# EasyRider.net
KiCad netlist of a schematic drawn in EAGLE
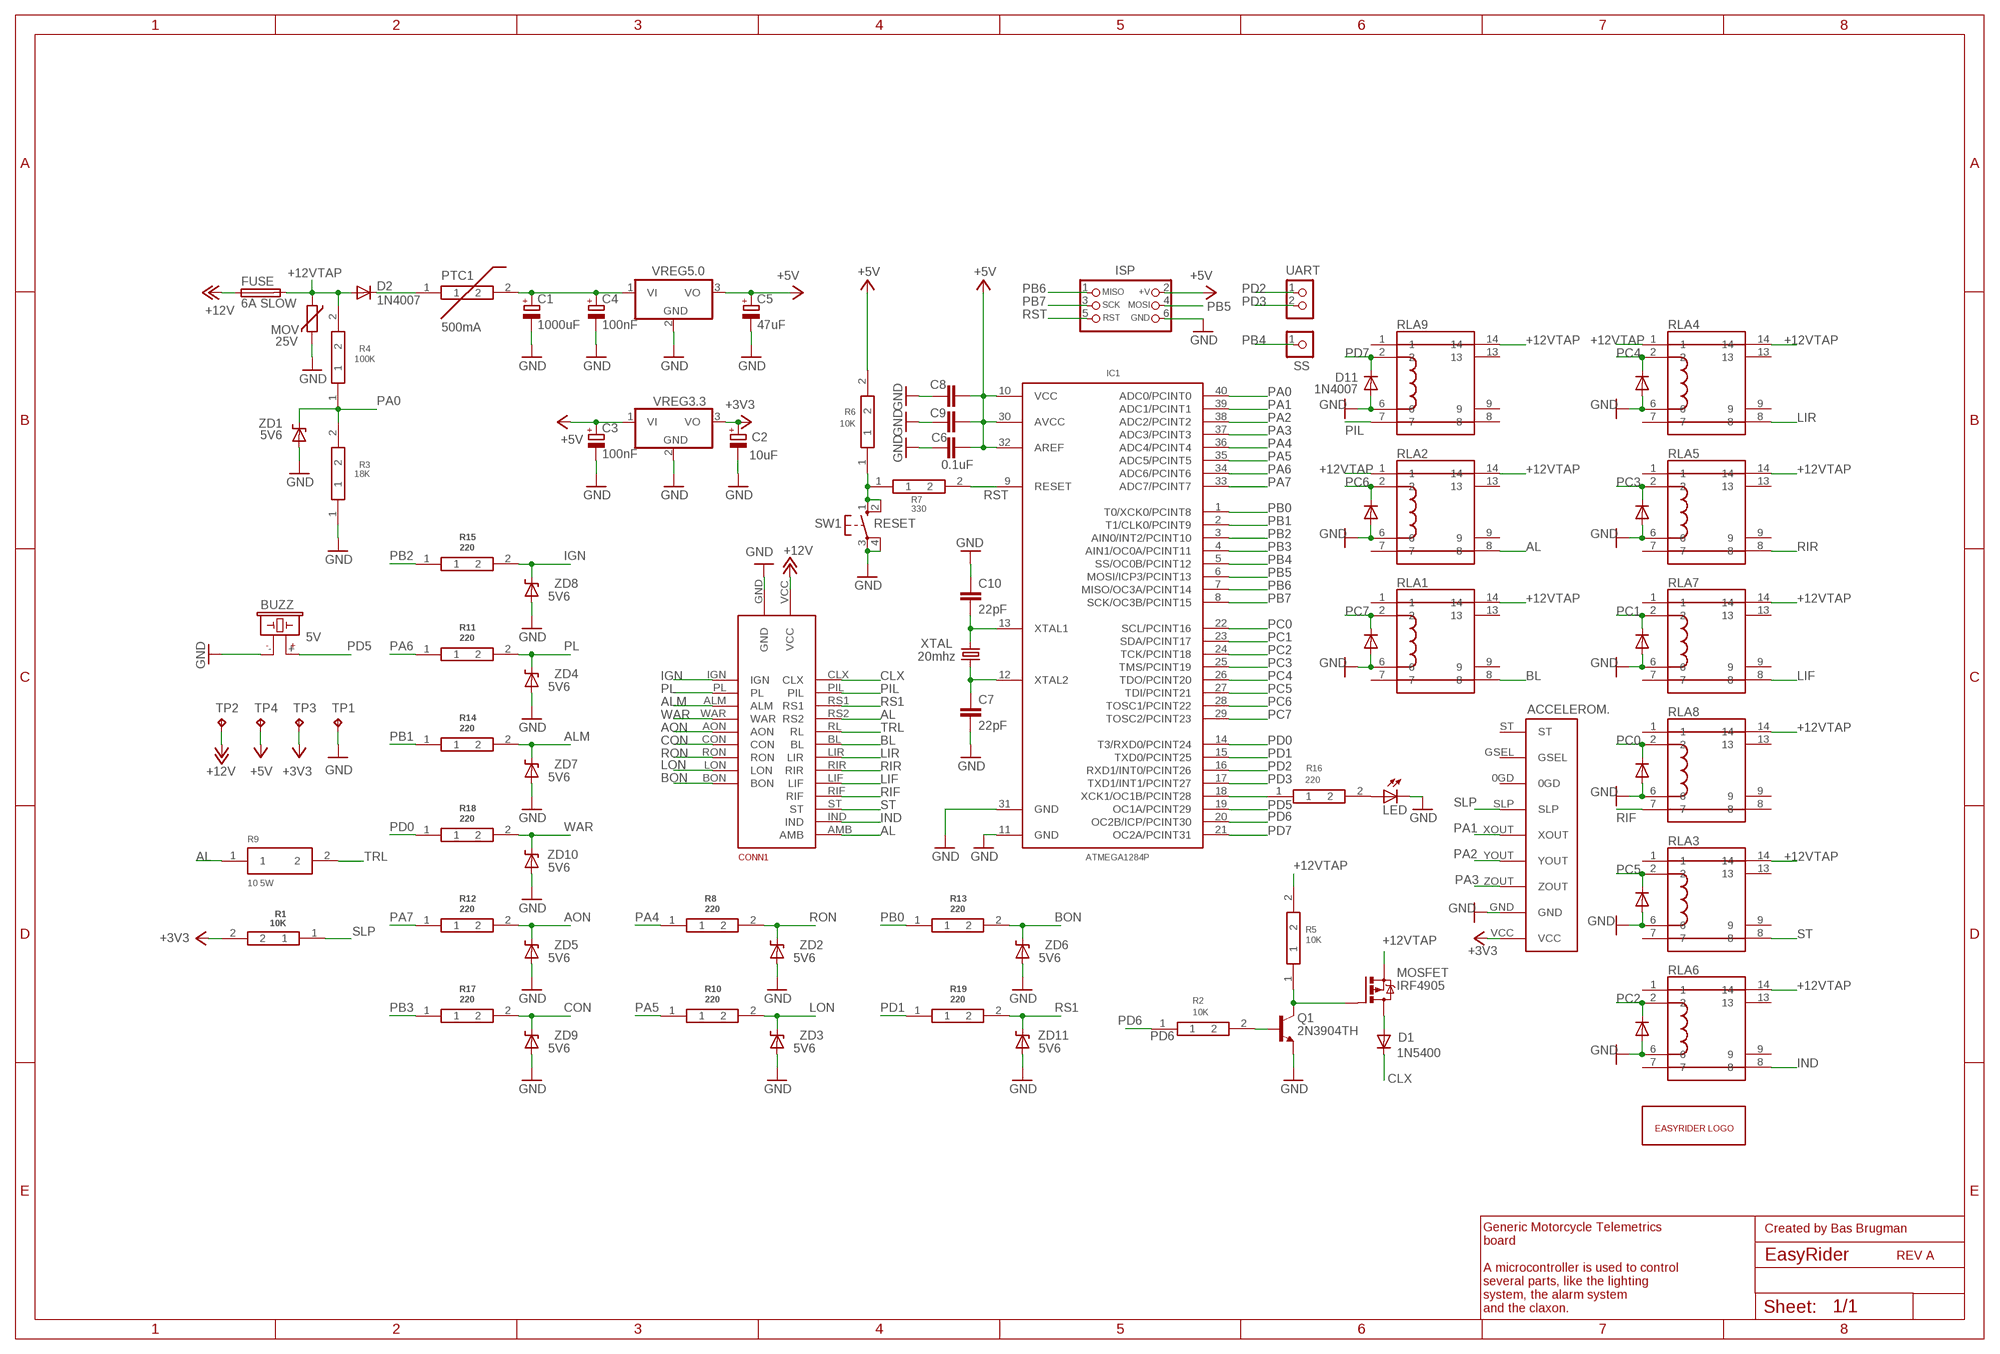
[diagram p0: schematic, sheet 1]

(export (version "E")
  (design (tool "Eeschema 10.0.6"))
  (components
    (comp (ref "ACCELEROM.")
      (value "MMA7361FREESCALE")
      (footprint "eagle-import:BREAKOUT")
      (libsource (lib "eagle-import") (part "ACCELBOARDSIL"))
    )
    (comp (ref "BUZZ")
      (value "5V")
      (footprint "eagle-import:0.3PITCH")
      (libsource (lib "eagle-import") (part "BUZZERDIP"))
    )
    (comp (ref "C1")
      (value "1000uF")
      (footprint "eagle-import:E5-10,5")
      (libsource (lib "eagle-import") (part "CAPACITOR_POL0.2PITCH"))
    )
    (comp (ref "C2")
      (value "10uF")
      (footprint "eagle-import:E2,5-4R")
      (libsource (lib "eagle-import") (part "CAPACITOR_POL0.1PITCH4MMDIA"))
    )
    (comp (ref "C3")
      (value "100nF")
      (footprint "eagle-import:E2,5-4R")
      (libsource (lib "eagle-import") (part "CAPACITOR_POL0.1PITCH4MMDIA"))
    )
    (comp (ref "C4")
      (value "100nF")
      (footprint "eagle-import:E2,5-4R")
      (libsource (lib "eagle-import") (part "CAPACITOR_POL0.1PITCH4MMDIA"))
    )
    (comp (ref "C5")
      (value "47uF")
      (footprint "eagle-import:E2,5-7")
      (libsource (lib "eagle-import") (part "CAPACITOR_POL0.1PITCH"))
    )
    (comp (ref "C6")
      (value "0.1uF")
      (footprint "eagle-import:C025-024X044")
      (libsource (lib "eagle-import") (part "CAPACITOR0.1PITCH"))
    )
    (comp (ref "C7")
      (value "22pF")
      (footprint "eagle-import:C025-024X044")
      (libsource (lib "eagle-import") (part "CAPACITOR0.1PITCH"))
    )
    (comp (ref "C8")
      (value "0.1uF")
      (footprint "eagle-import:C025-024X044")
      (libsource (lib "eagle-import") (part "CAPACITOR0.1PITCH"))
    )
    (comp (ref "C9")
      (value "0.1uF")
      (footprint "eagle-import:C025-024X044")
      (libsource (lib "eagle-import") (part "CAPACITOR0.1PITCH"))
    )
    (comp (ref "C10")
      (value "22pF")
      (footprint "eagle-import:C025-024X044")
      (libsource (lib "eagle-import") (part "CAPACITOR0.1PITCH"))
    )
    (comp (ref "CONN1")
      (value "EASYRIDER_CONNDIP")
      (footprint "eagle-import:SIL")
      (libsource (lib "eagle-import") (part "EASYRIDER_CONNDIP"))
    )
    (comp (ref "D1")
      (value "1N5400")
      (footprint "eagle-import:DO201-15")
      (libsource (lib "eagle-import") (part "1N5400DIP"))
    )
    (comp (ref "D2")
      (value "1N4007")
      (footprint "eagle-import:DIP_1N4007")
      (libsource (lib "eagle-import") (part "1N4007DIP"))
    )
    (comp (ref "D3")
      (value "1N4007DIP")
      (footprint "eagle-import:DIP_1N4007")
      (libsource (lib "eagle-import") (part "1N4007DIP"))
    )
    (comp (ref "D4")
      (value "1N4007DIP")
      (footprint "eagle-import:DIP_1N4007")
      (libsource (lib "eagle-import") (part "1N4007DIP"))
    )
    (comp (ref "D5")
      (value "1N4007DIP")
      (footprint "eagle-import:DIP_1N4007")
      (libsource (lib "eagle-import") (part "1N4007DIP"))
    )
    (comp (ref "D6")
      (value "1N4007DIP")
      (footprint "eagle-import:DIP_1N4007")
      (libsource (lib "eagle-import") (part "1N4007DIP"))
    )
    (comp (ref "D7")
      (value "1N4007DIP")
      (footprint "eagle-import:DIP_1N4007")
      (libsource (lib "eagle-import") (part "1N4007DIP"))
    )
    (comp (ref "D8")
      (value "1N4007DIP")
      (footprint "eagle-import:DIP_1N4007")
      (libsource (lib "eagle-import") (part "1N4007DIP"))
    )
    (comp (ref "D9")
      (value "1N4007DIP")
      (footprint "eagle-import:DIP_1N4007")
      (libsource (lib "eagle-import") (part "1N4007DIP"))
    )
    (comp (ref "D10")
      (value "1N4007DIP")
      (footprint "eagle-import:DIP_1N4007")
      (libsource (lib "eagle-import") (part "1N4007DIP"))
    )
    (comp (ref "D11")
      (value "1N4007")
      (footprint "eagle-import:DIP_1N4007")
      (libsource (lib "eagle-import") (part "1N4007DIP"))
    )
    (comp (ref "FUSE")
      (value "6A SLOW")
      (footprint "eagle-import:SH22,5A")
      (fields (field (name "MPN") "0031.7701.11"))
      (libsource (lib "eagle-import") (part "FUSE_HOLDER_225DIP"))
    )
    (comp (ref "IC1")
      (value "ATMEGA1284P")
      (footprint "eagle-import:DIL40")
      (libsource (lib "eagle-import") (part "MEGA1284PDIP"))
    )
    (comp (ref "ISP")
      (value "CON_HEADER_PRG_AVR_ICSP-PTH")
      (footprint "eagle-import:HEADER_PRG_2X03")
      (libsource (lib "eagle-import") (part "CON_HEADER_PRG_AVR_ICSP-PTH"))
    )
    (comp (ref "LED")
      (value "LEDDIP")
      (footprint "eagle-import:LED3MM")
      (libsource (lib "eagle-import") (part "LEDDIP"))
    )
    (comp (ref "MOSFET")
      (value "IRF4905")
      (footprint "eagle-import:TO220")
      (libsource (lib "eagle-import") (part "IRF4905TH"))
    )
    (comp (ref "MOV")
      (value "25V")
      (footprint "eagle-import:R-5")
      (libsource (lib "eagle-import") (part "VARISTORSIL"))
    )
    (comp (ref "PTC1")
      (value "500mA")
      (footprint "eagle-import:PTC")
      (libsource (lib "eagle-import") (part "PTCSMD"))
    )
    (comp (ref "Q1")
      (value "2N3904TH")
      (footprint "eagle-import:TO92")
      (libsource (lib "eagle-import") (part "2N3904TH"))
    )
    (comp (ref "R1")
      (value "10K")
      (footprint "eagle-import:RESISTOR")
      (libsource (lib "eagle-import") (part "RESISTOR_GENERICDIP"))
    )
    (comp (ref "R2")
      (value "10K")
      (footprint "eagle-import:RESISTOR")
      (libsource (lib "eagle-import") (part "RESISTOR_GENERICDIP"))
    )
    (comp (ref "R3")
      (value "18K")
      (footprint "eagle-import:RESISTOR")
      (libsource (lib "eagle-import") (part "RESISTOR_GENERICDIP"))
    )
    (comp (ref "R4")
      (value "100K")
      (footprint "eagle-import:RESISTOR")
      (libsource (lib "eagle-import") (part "RESISTOR_GENERICDIP"))
    )
    (comp (ref "R5")
      (value "10K")
      (footprint "eagle-import:RESISTOR")
      (libsource (lib "eagle-import") (part "RESISTOR_GENERICDIP"))
    )
    (comp (ref "R6")
      (value "10K")
      (footprint "eagle-import:RESISTOR")
      (libsource (lib "eagle-import") (part "RESISTOR_GENERICDIP"))
    )
    (comp (ref "R7")
      (value "330")
      (footprint "eagle-import:RESISTOR")
      (libsource (lib "eagle-import") (part "RESISTOR_GENERICDIP"))
    )
    (comp (ref "R8")
      (value "220")
      (footprint "eagle-import:RESISTOR")
      (libsource (lib "eagle-import") (part "RESISTOR_GENERICDIP"))
    )
    (comp (ref "R9")
      (value "10 5W")
      (footprint "eagle-import:RESISTOR")
      (libsource (lib "eagle-import") (part "RESISTOR_GENERIC_HIGH_WATTDIP"))
    )
    (comp (ref "R10")
      (value "220")
      (footprint "eagle-import:RESISTOR")
      (libsource (lib "eagle-import") (part "RESISTOR_GENERICDIP"))
    )
    (comp (ref "R11")
      (value "220")
      (footprint "eagle-import:RESISTOR")
      (libsource (lib "eagle-import") (part "RESISTOR_GENERICDIP"))
    )
    (comp (ref "R12")
      (value "220")
      (footprint "eagle-import:RESISTOR")
      (libsource (lib "eagle-import") (part "RESISTOR_GENERICDIP"))
    )
    (comp (ref "R13")
      (value "220")
      (footprint "eagle-import:RESISTOR")
      (libsource (lib "eagle-import") (part "RESISTOR_GENERICDIP"))
    )
    (comp (ref "R14")
      (value "220")
      (footprint "eagle-import:RESISTOR")
      (libsource (lib "eagle-import") (part "RESISTOR_GENERICDIP"))
    )
    (comp (ref "R15")
      (value "220")
      (footprint "eagle-import:RESISTOR")
      (libsource (lib "eagle-import") (part "RESISTOR_GENERICDIP"))
    )
    (comp (ref "R16")
      (value "220")
      (footprint "eagle-import:RESISTOR")
      (libsource (lib "eagle-import") (part "RESISTOR_GENERICDIP"))
    )
    (comp (ref "R17")
      (value "220")
      (footprint "eagle-import:RESISTOR")
      (libsource (lib "eagle-import") (part "RESISTOR_GENERICDIP"))
    )
    (comp (ref "R18")
      (value "220")
      (footprint "eagle-import:RESISTOR")
      (libsource (lib "eagle-import") (part "RESISTOR_GENERICDIP"))
    )
    (comp (ref "R19")
      (value "220")
      (footprint "eagle-import:RESISTOR")
      (libsource (lib "eagle-import") (part "RESISTOR_GENERICDIP"))
    )
    (comp (ref "RLA1")
      (value "MEDER_REED_DIP05-1A72-12LDIP")
      (footprint "eagle-import:DIP05-1A72-12L")
      (libsource (lib "eagle-import") (part "MEDER_REED_DIP05-1A72-12LDIP"))
    )
    (comp (ref "RLA2")
      (value "MEDER_REED_DIP05-1A72-12LDIP")
      (footprint "eagle-import:DIP05-1A72-12L")
      (libsource (lib "eagle-import") (part "MEDER_REED_DIP05-1A72-12LDIP"))
    )
    (comp (ref "RLA3")
      (value "MEDER_REED_DIP05-1A72-12LDIP")
      (footprint "eagle-import:DIP05-1A72-12L")
      (libsource (lib "eagle-import") (part "MEDER_REED_DIP05-1A72-12LDIP"))
    )
    (comp (ref "RLA4")
      (value "MEDER_REED_DIP05-1A72-12LDIP")
      (footprint "eagle-import:DIP05-1A72-12L")
      (libsource (lib "eagle-import") (part "MEDER_REED_DIP05-1A72-12LDIP"))
    )
    (comp (ref "RLA5")
      (value "MEDER_REED_DIP05-1A72-12LDIP")
      (footprint "eagle-import:DIP05-1A72-12L")
      (libsource (lib "eagle-import") (part "MEDER_REED_DIP05-1A72-12LDIP"))
    )
    (comp (ref "RLA6")
      (value "MEDER_REED_DIP05-1A72-12LDIP")
      (footprint "eagle-import:DIP05-1A72-12L")
      (libsource (lib "eagle-import") (part "MEDER_REED_DIP05-1A72-12LDIP"))
    )
    (comp (ref "RLA7")
      (value "MEDER_REED_DIP05-1A72-12LDIP")
      (footprint "eagle-import:DIP05-1A72-12L")
      (libsource (lib "eagle-import") (part "MEDER_REED_DIP05-1A72-12LDIP"))
    )
    (comp (ref "RLA8")
      (value "MEDER_REED_DIP05-1A72-12LDIP")
      (footprint "eagle-import:DIP05-1A72-12L")
      (libsource (lib "eagle-import") (part "MEDER_REED_DIP05-1A72-12LDIP"))
    )
    (comp (ref "RLA9")
      (value "MEDER_REED_DIP05-1A72-12LDIP")
      (footprint "eagle-import:DIP05-1A72-12L")
      (libsource (lib "eagle-import") (part "MEDER_REED_DIP05-1A72-12LDIP"))
    )
    (comp (ref "SS")
      (value "CON_HEADER_1X01-PTH")
      (footprint "eagle-import:M1X1")
      (libsource (lib "eagle-import") (part "CON_HEADER_1X01-PTH"))
    )
    (comp (ref "SW1")
      (value "RESET")
      (footprint "eagle-import:DIP45MM_56MM_PITCH")
      (fields (field (name "MPN") "B3F-1000"))
      (libsource (lib "eagle-import") (part "10-XXDIP"))
    )
    (comp (ref "TP1")
      (value "TPTP20SQ")
      (footprint "eagle-import:TP20SQ")
      (libsource (lib "eagle-import") (part "TPTP20SQ"))
    )
    (comp (ref "TP2")
      (value "TPTP20SQ")
      (footprint "eagle-import:TP20SQ")
      (libsource (lib "eagle-import") (part "TPTP20SQ"))
    )
    (comp (ref "TP3")
      (value "TPTP20SQ")
      (footprint "eagle-import:TP20SQ")
      (libsource (lib "eagle-import") (part "TPTP20SQ"))
    )
    (comp (ref "TP4")
      (value "TPTP20SQ")
      (footprint "eagle-import:TP20SQ")
      (libsource (lib "eagle-import") (part "TPTP20SQ"))
    )
    (comp (ref "U$1")
      (value "EASYRIDER_LOGO")
      (footprint "eagle-import:EASYRIDER_LOGO")
      (libsource (lib "eagle-import") (part "EASYRIDER_LOGO"))
    )
    (comp (ref "UART")
      (value "CON_HEADER_1X02-PTH")
      (footprint "eagle-import:M1X2")
      (libsource (lib "eagle-import") (part "CON_HEADER_1X02-PTH"))
    )
    (comp (ref "VREG3.3")
      (value "VREG_IGODIP")
      (footprint "eagle-import:TO220")
      (libsource (lib "eagle-import") (part "VREG_IGODIP"))
    )
    (comp (ref "VREG5.0")
      (value "VREG_IGODIP")
      (footprint "eagle-import:TO220")
      (libsource (lib "eagle-import") (part "VREG_IGODIP"))
    )
    (comp (ref "XTAL")
      (value "20mhz")
      (footprint "eagle-import:HC49_S")
      (libsource (lib "eagle-import") (part "CRYSTALDIP"))
    )
    (comp (ref "ZD1")
      (value "5V6")
      (footprint "eagle-import:DIODE_ZENER_56")
      (libsource (lib "eagle-import") (part "DIODE_ZENER_56DIP"))
    )
    (comp (ref "ZD2")
      (value "5V6")
      (footprint "eagle-import:DIODE_ZENER_56")
      (libsource (lib "eagle-import") (part "DIODE_ZENER_56DIP"))
    )
    (comp (ref "ZD3")
      (value "5V6")
      (footprint "eagle-import:DIODE_ZENER_56")
      (libsource (lib "eagle-import") (part "DIODE_ZENER_56DIP"))
    )
    (comp (ref "ZD4")
      (value "5V6")
      (footprint "eagle-import:DIODE_ZENER_56")
      (libsource (lib "eagle-import") (part "DIODE_ZENER_56DIP"))
    )
    (comp (ref "ZD5")
      (value "5V6")
      (footprint "eagle-import:DIODE_ZENER_56")
      (libsource (lib "eagle-import") (part "DIODE_ZENER_56DIP"))
    )
    (comp (ref "ZD6")
      (value "5V6")
      (footprint "eagle-import:DIODE_ZENER_56")
      (libsource (lib "eagle-import") (part "DIODE_ZENER_56DIP"))
    )
    (comp (ref "ZD7")
      (value "5V6")
      (footprint "eagle-import:DIODE_ZENER_56")
      (libsource (lib "eagle-import") (part "DIODE_ZENER_56DIP"))
    )
    (comp (ref "ZD8")
      (value "5V6")
      (footprint "eagle-import:DIODE_ZENER_56")
      (libsource (lib "eagle-import") (part "DIODE_ZENER_56DIP"))
    )
    (comp (ref "ZD9")
      (value "5V6")
      (footprint "eagle-import:DIODE_ZENER_56")
      (libsource (lib "eagle-import") (part "DIODE_ZENER_56DIP"))
    )
    (comp (ref "ZD10")
      (value "5V6")
      (footprint "eagle-import:DIODE_ZENER_56")
      (libsource (lib "eagle-import") (part "DIODE_ZENER_56DIP"))
    )
    (comp (ref "ZD11")
      (value "5V6")
      (footprint "eagle-import:DIODE_ZENER_56")
      (libsource (lib "eagle-import") (part "DIODE_ZENER_56DIP"))
    )
  )
  (nets
    (net (code "1") (name "+3V3") (class "Default")
      (node (ref "ACCELEROM.") (pin "VCC") (pinfunction "VCC_VCC") (pintype "bidirectional"))
      (node (ref "C2") (pin "+") (pinfunction "+_+") (pintype "passive"))
      (node (ref "R1") (pin "2") (pinfunction "2_2") (pintype "bidirectional"))
      (node (ref "TP3") (pin "TP") (pinfunction "TP_TP") (pintype "input"))
      (node (ref "VREG3.3") (pin "3") (pinfunction "VO_3") (pintype "passive"))
    )
    (net (code "2") (name "+5V") (class "Default")
      (node (ref "C3") (pin "+") (pinfunction "+_+") (pintype "passive"))
      (node (ref "C5") (pin "+") (pinfunction "+_+") (pintype "passive"))
      (node (ref "C6") (pin "2") (pinfunction "2_2") (pintype "passive"))
      (node (ref "C8") (pin "2") (pinfunction "2_2") (pintype "passive"))
      (node (ref "C9") (pin "2") (pinfunction "2_2") (pintype "passive"))
      (node (ref "IC1") (pin "10") (pinfunction "VCC_10") (pintype "bidirectional"))
      (node (ref "IC1") (pin "30") (pinfunction "AVCC_30") (pintype "bidirectional"))
      (node (ref "IC1") (pin "32") (pinfunction "AREF_32") (pintype "bidirectional"))
      (node (ref "ISP") (pin "2") (pinfunction "+V_2") (pintype "passive"))
      (node (ref "R6") (pin "2") (pinfunction "2_2") (pintype "bidirectional"))
      (node (ref "TP4") (pin "TP") (pinfunction "TP_TP") (pintype "input"))
      (node (ref "VREG3.3") (pin "1") (pinfunction "VI_1") (pintype "input"))
      (node (ref "VREG5.0") (pin "3") (pinfunction "VO_3") (pintype "passive"))
    )
    (net (code "3") (name "+12V") (class "Default")
      (node (ref "CONN1") (pin "VCC") (pinfunction "VCC_VCC") (pintype "bidirectional"))
      (node (ref "FUSE") (pin "1") (pinfunction "1_1") (pintype "passive"))
      (node (ref "TP2") (pin "TP") (pinfunction "TP_TP") (pintype "input"))
    )
    (net (code "4") (name "/+12VTAP") (class "Default")
      (node (ref "D2") (pin "A") (pinfunction "A_A") (pintype "passive"))
      (node (ref "FUSE") (pin "2") (pinfunction "2_2") (pintype "passive"))
      (node (ref "MOSFET") (pin "S") (pinfunction "S_S") (pintype "passive"))
      (node (ref "MOV") (pin "1") (pinfunction "1_1") (pintype "passive"))
      (node (ref "R4") (pin "2") (pinfunction "2_2") (pintype "bidirectional"))
      (node (ref "R5") (pin "2") (pinfunction "2_2") (pintype "bidirectional"))
      (node (ref "RLA1") (pin "14") (pinfunction "14_14") (pintype "bidirectional"))
      (node (ref "RLA2") (pin "1") (pinfunction "1_1") (pintype "bidirectional"))
      (node (ref "RLA2") (pin "14") (pinfunction "14_14") (pintype "bidirectional"))
      (node (ref "RLA3") (pin "14") (pinfunction "14_14") (pintype "bidirectional"))
      (node (ref "RLA4") (pin "1") (pinfunction "1_1") (pintype "bidirectional"))
      (node (ref "RLA4") (pin "14") (pinfunction "14_14") (pintype "bidirectional"))
      (node (ref "RLA5") (pin "14") (pinfunction "14_14") (pintype "bidirectional"))
      (node (ref "RLA6") (pin "14") (pinfunction "14_14") (pintype "bidirectional"))
      (node (ref "RLA7") (pin "14") (pinfunction "14_14") (pintype "bidirectional"))
      (node (ref "RLA8") (pin "14") (pinfunction "14_14") (pintype "bidirectional"))
      (node (ref "RLA9") (pin "14") (pinfunction "14_14") (pintype "bidirectional"))
    )
    (net (code "5") (name "/AL") (class "Default")
      (node (ref "CONN1") (pin "AMB") (pinfunction "AMB_AMB") (pintype "bidirectional"))
      (node (ref "CONN1") (pin "RS2") (pinfunction "RS2_RS2") (pintype "bidirectional"))
      (node (ref "R9") (pin "1") (pinfunction "1_1") (pintype "bidirectional"))
      (node (ref "RLA2") (pin "8") (pinfunction "8_8") (pintype "bidirectional"))
    )
    (net (code "6") (name "/ALM") (class "Default")
      (node (ref "CONN1") (pin "ALM") (pinfunction "ALM_ALM") (pintype "bidirectional"))
      (node (ref "R14") (pin "2") (pinfunction "2_2") (pintype "bidirectional"))
      (node (ref "ZD7") (pin "C") (pinfunction "C_C") (pintype "passive"))
    )
    (net (code "7") (name "/AON") (class "Default")
      (node (ref "CONN1") (pin "AON") (pinfunction "AON_AON") (pintype "bidirectional"))
      (node (ref "R12") (pin "2") (pinfunction "2_2") (pintype "bidirectional"))
      (node (ref "ZD5") (pin "C") (pinfunction "C_C") (pintype "passive"))
    )
    (net (code "8") (name "/BL") (class "Default")
      (node (ref "CONN1") (pin "BL") (pinfunction "BL_BL") (pintype "bidirectional"))
      (node (ref "RLA1") (pin "8") (pinfunction "8_8") (pintype "bidirectional"))
    )
    (net (code "9") (name "/BON") (class "Default")
      (node (ref "CONN1") (pin "BON") (pinfunction "BON_BON") (pintype "bidirectional"))
      (node (ref "R13") (pin "2") (pinfunction "2_2") (pintype "bidirectional"))
      (node (ref "ZD6") (pin "C") (pinfunction "C_C") (pintype "passive"))
    )
    (net (code "10") (name "/CLX") (class "Default")
      (node (ref "CONN1") (pin "CLX") (pinfunction "CLX_CLX") (pintype "bidirectional"))
      (node (ref "D1") (pin "C") (pinfunction "C_C") (pintype "passive"))
    )
    (net (code "11") (name "/CON") (class "Default")
      (node (ref "CONN1") (pin "CON") (pinfunction "CON_CON") (pintype "bidirectional"))
      (node (ref "R17") (pin "2") (pinfunction "2_2") (pintype "bidirectional"))
      (node (ref "ZD9") (pin "C") (pinfunction "C_C") (pintype "passive"))
    )
    (net (code "12") (name "/IGN") (class "Default")
      (node (ref "CONN1") (pin "IGN") (pinfunction "IGN_IGN") (pintype "bidirectional"))
      (node (ref "R15") (pin "2") (pinfunction "2_2") (pintype "bidirectional"))
      (node (ref "ZD8") (pin "C") (pinfunction "C_C") (pintype "passive"))
    )
    (net (code "13") (name "/IND") (class "Default")
      (node (ref "CONN1") (pin "IND") (pinfunction "IND_IND") (pintype "bidirectional"))
      (node (ref "RLA6") (pin "8") (pinfunction "8_8") (pintype "bidirectional"))
    )
    (net (code "14") (name "/LIF") (class "Default")
      (node (ref "CONN1") (pin "LIF") (pinfunction "LIF_LIF") (pintype "bidirectional"))
      (node (ref "RLA7") (pin "8") (pinfunction "8_8") (pintype "bidirectional"))
    )
    (net (code "15") (name "/LIR") (class "Default")
      (node (ref "CONN1") (pin "LIR") (pinfunction "LIR_LIR") (pintype "bidirectional"))
      (node (ref "RLA4") (pin "8") (pinfunction "8_8") (pintype "bidirectional"))
    )
    (net (code "16") (name "/LON") (class "Default")
      (node (ref "CONN1") (pin "LON") (pinfunction "LON_LON") (pintype "bidirectional"))
      (node (ref "R10") (pin "2") (pinfunction "2_2") (pintype "bidirectional"))
      (node (ref "ZD3") (pin "C") (pinfunction "C_C") (pintype "passive"))
    )
    (net (code "17") (name "/PA0") (class "Default")
      (node (ref "IC1") (pin "40") (pinfunction "ADC0/PCINT0_40") (pintype "bidirectional"))
      (node (ref "R3") (pin "2") (pinfunction "2_2") (pintype "bidirectional"))
      (node (ref "R4") (pin "1") (pinfunction "1_1") (pintype "bidirectional"))
      (node (ref "ZD1") (pin "C") (pinfunction "C_C") (pintype "passive"))
    )
    (net (code "18") (name "/PA1") (class "Default")
      (node (ref "ACCELEROM.") (pin "XOUT") (pinfunction "XOUT_XOUT") (pintype "bidirectional"))
      (node (ref "IC1") (pin "39") (pinfunction "ADC1/PCINT1_39") (pintype "bidirectional"))
    )
    (net (code "19") (name "/PA2") (class "Default")
      (node (ref "ACCELEROM.") (pin "YOUT") (pinfunction "YOUT_YOUT") (pintype "bidirectional"))
      (node (ref "IC1") (pin "38") (pinfunction "ADC2/PCINT2_38") (pintype "bidirectional"))
    )
    (net (code "20") (name "/PA3") (class "Default")
      (node (ref "ACCELEROM.") (pin "ZOUT") (pinfunction "ZOUT_ZOUT") (pintype "bidirectional"))
      (node (ref "IC1") (pin "37") (pinfunction "ADC3/PCINT3_37") (pintype "bidirectional"))
    )
    (net (code "21") (name "/PA4") (class "Default")
      (node (ref "IC1") (pin "36") (pinfunction "ADC4/PCINT4_36") (pintype "bidirectional"))
      (node (ref "R8") (pin "1") (pinfunction "1_1") (pintype "bidirectional"))
    )
    (net (code "22") (name "/PA5") (class "Default")
      (node (ref "IC1") (pin "35") (pinfunction "ADC5/PCINT5_35") (pintype "bidirectional"))
      (node (ref "R10") (pin "1") (pinfunction "1_1") (pintype "bidirectional"))
    )
    (net (code "23") (name "/PA6") (class "Default")
      (node (ref "IC1") (pin "34") (pinfunction "ADC6/PCINT6_34") (pintype "bidirectional"))
      (node (ref "R11") (pin "1") (pinfunction "1_1") (pintype "bidirectional"))
    )
    (net (code "24") (name "/PA7") (class "Default")
      (node (ref "IC1") (pin "33") (pinfunction "ADC7/PCINT7_33") (pintype "bidirectional"))
      (node (ref "R12") (pin "1") (pinfunction "1_1") (pintype "bidirectional"))
    )
    (net (code "25") (name "/PB0") (class "Default")
      (node (ref "IC1") (pin "1") (pinfunction "T0/XCK0/PCINT8_1") (pintype "bidirectional"))
      (node (ref "R13") (pin "1") (pinfunction "1_1") (pintype "bidirectional"))
    )
    (net (code "26") (name "/PB1") (class "Default")
      (node (ref "IC1") (pin "2") (pinfunction "T1/CLK0/PCINT9_2") (pintype "bidirectional"))
      (node (ref "R14") (pin "1") (pinfunction "1_1") (pintype "bidirectional"))
    )
    (net (code "27") (name "/PB2") (class "Default")
      (node (ref "IC1") (pin "3") (pinfunction "AIN0/INT2/PCINT10_3") (pintype "bidirectional"))
      (node (ref "R15") (pin "1") (pinfunction "1_1") (pintype "bidirectional"))
    )
    (net (code "28") (name "/PB3") (class "Default")
      (node (ref "IC1") (pin "4") (pinfunction "AIN1/OC0A/PCINT11_4") (pintype "bidirectional"))
      (node (ref "R17") (pin "1") (pinfunction "1_1") (pintype "bidirectional"))
    )
    (net (code "29") (name "/PB4") (class "Default")
      (node (ref "IC1") (pin "5") (pinfunction "SS/OC0B/PCINT12_5") (pintype "bidirectional"))
      (node (ref "SS") (pin "1") (pinfunction "1_1") (pintype "passive"))
    )
    (net (code "30") (name "/PB5") (class "Default")
      (node (ref "IC1") (pin "6") (pinfunction "MOSI/ICP3/PCINT13_6") (pintype "bidirectional"))
      (node (ref "ISP") (pin "4") (pinfunction "MOSI_4") (pintype "passive"))
    )
    (net (code "31") (name "/PB6") (class "Default")
      (node (ref "IC1") (pin "7") (pinfunction "MISO/OC3A/PCINT14_7") (pintype "bidirectional"))
      (node (ref "ISP") (pin "1") (pinfunction "MISO_1") (pintype "passive"))
    )
    (net (code "32") (name "/PB7") (class "Default")
      (node (ref "IC1") (pin "8") (pinfunction "SCK/OC3B/PCINT15_8") (pintype "bidirectional"))
      (node (ref "ISP") (pin "3") (pinfunction "SCK_3") (pintype "passive"))
    )
    (net (code "33") (name "/PC0") (class "Default")
      (node (ref "D10") (pin "C") (pinfunction "C_C") (pintype "passive"))
      (node (ref "IC1") (pin "22") (pinfunction "SCL/PCINT16_22") (pintype "bidirectional"))
      (node (ref "RLA8") (pin "2") (pinfunction "2_2") (pintype "bidirectional"))
    )
    (net (code "34") (name "/PC1") (class "Default")
      (node (ref "D9") (pin "C") (pinfunction "C_C") (pintype "passive"))
      (node (ref "IC1") (pin "23") (pinfunction "SDA/PCINT17_23") (pintype "bidirectional"))
      (node (ref "RLA7") (pin "2") (pinfunction "2_2") (pintype "bidirectional"))
    )
    (net (code "35") (name "/PC2") (class "Default")
      (node (ref "D8") (pin "C") (pinfunction "C_C") (pintype "passive"))
      (node (ref "IC1") (pin "24") (pinfunction "TCK/PCINT18_24") (pintype "bidirectional"))
      (node (ref "RLA6") (pin "2") (pinfunction "2_2") (pintype "bidirectional"))
    )
    (net (code "36") (name "/PC3") (class "Default")
      (node (ref "D7") (pin "C") (pinfunction "C_C") (pintype "passive"))
      (node (ref "IC1") (pin "25") (pinfunction "TMS/PCINT19_25") (pintype "bidirectional"))
      (node (ref "RLA5") (pin "2") (pinfunction "2_2") (pintype "bidirectional"))
    )
    (net (code "37") (name "/PC4") (class "Default")
      (node (ref "D6") (pin "C") (pinfunction "C_C") (pintype "passive"))
      (node (ref "IC1") (pin "26") (pinfunction "TDO/PCINT20_26") (pintype "bidirectional"))
      (node (ref "RLA4") (pin "2") (pinfunction "2_2") (pintype "bidirectional"))
    )
    (net (code "38") (name "/PC5") (class "Default")
      (node (ref "D5") (pin "C") (pinfunction "C_C") (pintype "passive"))
      (node (ref "IC1") (pin "27") (pinfunction "TDI/PCINT21_27") (pintype "bidirectional"))
      (node (ref "RLA3") (pin "2") (pinfunction "2_2") (pintype "bidirectional"))
    )
    (net (code "39") (name "/PC6") (class "Default")
      (node (ref "D4") (pin "C") (pinfunction "C_C") (pintype "passive"))
      (node (ref "IC1") (pin "28") (pinfunction "TOSC1/PCINT22_28") (pintype "bidirectional"))
      (node (ref "RLA2") (pin "2") (pinfunction "2_2") (pintype "bidirectional"))
    )
    (net (code "40") (name "/PC7") (class "Default")
      (node (ref "D3") (pin "C") (pinfunction "C_C") (pintype "passive"))
      (node (ref "IC1") (pin "29") (pinfunction "TOSC2/PCINT23_29") (pintype "bidirectional"))
      (node (ref "RLA1") (pin "2") (pinfunction "2_2") (pintype "bidirectional"))
    )
    (net (code "41") (name "/PD0") (class "Default")
      (node (ref "IC1") (pin "14") (pinfunction "T3/RXD0/PCINT24_14") (pintype "bidirectional"))
      (node (ref "R18") (pin "1") (pinfunction "1_1") (pintype "bidirectional"))
    )
    (net (code "42") (name "/PD1") (class "Default")
      (node (ref "IC1") (pin "15") (pinfunction "TXD0/PCINT25_15") (pintype "bidirectional"))
      (node (ref "R19") (pin "1") (pinfunction "1_1") (pintype "bidirectional"))
    )
    (net (code "43") (name "/PD2") (class "Default")
      (node (ref "IC1") (pin "16") (pinfunction "RXD1/INT0/PCINT26_16") (pintype "bidirectional"))
      (node (ref "UART") (pin "1") (pinfunction "1_1") (pintype "passive"))
    )
    (net (code "44") (name "/PD3") (class "Default")
      (node (ref "IC1") (pin "17") (pinfunction "TXD1/INT1/PCINT27_17") (pintype "bidirectional"))
      (node (ref "UART") (pin "2") (pinfunction "2_2") (pintype "passive"))
    )
    (net (code "45") (name "/PD5") (class "Default")
      (node (ref "BUZZ") (pin "+") (pinfunction "2_+") (pintype "passive"))
      (node (ref "IC1") (pin "19") (pinfunction "OC1A/PCINT29_19") (pintype "bidirectional"))
    )
    (net (code "46") (name "/PD6") (class "Default")
      (node (ref "IC1") (pin "20") (pinfunction "OC2B/ICP/PCINT30_20") (pintype "bidirectional"))
      (node (ref "R2") (pin "1") (pinfunction "1_1") (pintype "bidirectional"))
    )
    (net (code "47") (name "/PD7") (class "Default")
      (node (ref "D11") (pin "C") (pinfunction "C_C") (pintype "passive"))
      (node (ref "IC1") (pin "21") (pinfunction "OC2A/PCINT31_21") (pintype "bidirectional"))
      (node (ref "RLA9") (pin "2") (pinfunction "2_2") (pintype "bidirectional"))
    )
    (net (code "48") (name "/PIL") (class "Default")
      (node (ref "CONN1") (pin "PIL") (pinfunction "PIL_PIL") (pintype "bidirectional"))
      (node (ref "RLA9") (pin "7") (pinfunction "7_7") (pintype "bidirectional"))
    )
    (net (code "49") (name "/PL") (class "Default")
      (node (ref "CONN1") (pin "PL") (pinfunction "PL_PL") (pintype "bidirectional"))
      (node (ref "R11") (pin "2") (pinfunction "2_2") (pintype "bidirectional"))
      (node (ref "ZD4") (pin "C") (pinfunction "C_C") (pintype "passive"))
    )
    (net (code "50") (name "/RIF") (class "Default")
      (node (ref "CONN1") (pin "RIF") (pinfunction "RIF_RIF") (pintype "bidirectional"))
      (node (ref "RLA8") (pin "7") (pinfunction "7_7") (pintype "bidirectional"))
    )
    (net (code "51") (name "/RIR") (class "Default")
      (node (ref "CONN1") (pin "RIR") (pinfunction "RIR_RIR") (pintype "bidirectional"))
      (node (ref "RLA5") (pin "8") (pinfunction "8_8") (pintype "bidirectional"))
    )
    (net (code "52") (name "/RON") (class "Default")
      (node (ref "CONN1") (pin "RON") (pinfunction "RON_RON") (pintype "bidirectional"))
      (node (ref "R8") (pin "2") (pinfunction "2_2") (pintype "bidirectional"))
      (node (ref "ZD2") (pin "C") (pinfunction "C_C") (pintype "passive"))
    )
    (net (code "53") (name "/RS1") (class "Default")
      (node (ref "CONN1") (pin "RS1") (pinfunction "RS1_RS1") (pintype "bidirectional"))
      (node (ref "R19") (pin "2") (pinfunction "2_2") (pintype "bidirectional"))
      (node (ref "ZD11") (pin "C") (pinfunction "C_C") (pintype "passive"))
    )
    (net (code "54") (name "/RST") (class "Default")
      (node (ref "IC1") (pin "9") (pinfunction "RESET_9") (pintype "bidirectional"))
      (node (ref "ISP") (pin "5") (pinfunction "RST_5") (pintype "passive"))
      (node (ref "R7") (pin "2") (pinfunction "2_2") (pintype "bidirectional"))
    )
    (net (code "55") (name "/SLP") (class "Default")
      (node (ref "ACCELEROM.") (pin "SLP") (pinfunction "SLP_SLP") (pintype "bidirectional"))
      (node (ref "R1") (pin "1") (pinfunction "1_1") (pintype "bidirectional"))
    )
    (net (code "56") (name "/ST") (class "Default")
      (node (ref "CONN1") (pin "ST") (pinfunction "ST_ST") (pintype "bidirectional"))
      (node (ref "RLA3") (pin "8") (pinfunction "8_8") (pintype "bidirectional"))
    )
    (net (code "57") (name "/TRL") (class "Default")
      (node (ref "CONN1") (pin "RL") (pinfunction "RL_RL") (pintype "bidirectional"))
      (node (ref "R9") (pin "2") (pinfunction "2_2") (pintype "bidirectional"))
    )
    (net (code "58") (name "/WAR") (class "Default")
      (node (ref "CONN1") (pin "WAR") (pinfunction "WAR_WAR") (pintype "bidirectional"))
      (node (ref "R18") (pin "2") (pinfunction "2_2") (pintype "bidirectional"))
      (node (ref "ZD10") (pin "C") (pinfunction "C_C") (pintype "passive"))
    )
    (net (code "59") (name "GND") (class "Default")
      (node (ref "ACCELEROM.") (pin "GND") (pinfunction "GND_GND") (pintype "bidirectional"))
      (node (ref "BUZZ") (pin "-") (pinfunction "1_-") (pintype "passive"))
      (node (ref "C1") (pin "-") (pinfunction "-_-") (pintype "passive"))
      (node (ref "C10") (pin "1") (pinfunction "1_1") (pintype "passive"))
      (node (ref "C2") (pin "-") (pinfunction "-_-") (pintype "passive"))
      (node (ref "C3") (pin "-") (pinfunction "-_-") (pintype "passive"))
      (node (ref "C4") (pin "-") (pinfunction "-_-") (pintype "passive"))
      (node (ref "C5") (pin "-") (pinfunction "-_-") (pintype "passive"))
      (node (ref "C6") (pin "1") (pinfunction "1_1") (pintype "passive"))
      (node (ref "C7") (pin "2") (pinfunction "2_2") (pintype "passive"))
      (node (ref "C8") (pin "1") (pinfunction "1_1") (pintype "passive"))
      (node (ref "C9") (pin "1") (pinfunction "1_1") (pintype "passive"))
      (node (ref "CONN1") (pin "GND") (pinfunction "GND_GND") (pintype "bidirectional"))
      (node (ref "D10") (pin "A") (pinfunction "A_A") (pintype "passive"))
      (node (ref "D11") (pin "A") (pinfunction "A_A") (pintype "passive"))
      (node (ref "D3") (pin "A") (pinfunction "A_A") (pintype "passive"))
      (node (ref "D4") (pin "A") (pinfunction "A_A") (pintype "passive"))
      (node (ref "D5") (pin "A") (pinfunction "A_A") (pintype "passive"))
      (node (ref "D6") (pin "A") (pinfunction "A_A") (pintype "passive"))
      (node (ref "D7") (pin "A") (pinfunction "A_A") (pintype "passive"))
      (node (ref "D8") (pin "A") (pinfunction "A_A") (pintype "passive"))
      (node (ref "D9") (pin "A") (pinfunction "A_A") (pintype "passive"))
      (node (ref "IC1") (pin "11") (pinfunction "GND_11") (pintype "bidirectional"))
      (node (ref "IC1") (pin "31") (pinfunction "GND_31") (pintype "bidirectional"))
      (node (ref "ISP") (pin "6") (pinfunction "GND_6") (pintype "passive"))
      (node (ref "LED") (pin "K") (pinfunction "C_K") (pintype "passive"))
      (node (ref "MOV") (pin "2") (pinfunction "2_2") (pintype "passive"))
      (node (ref "Q1") (pin "3") (pinfunction "E_3") (pintype "passive"))
      (node (ref "R3") (pin "1") (pinfunction "1_1") (pintype "bidirectional"))
      (node (ref "RLA1") (pin "6") (pinfunction "6_6") (pintype "bidirectional"))
      (node (ref "RLA2") (pin "6") (pinfunction "6_6") (pintype "bidirectional"))
      (node (ref "RLA3") (pin "6") (pinfunction "6_6") (pintype "bidirectional"))
      (node (ref "RLA4") (pin "6") (pinfunction "6_6") (pintype "bidirectional"))
      (node (ref "RLA5") (pin "6") (pinfunction "6_6") (pintype "bidirectional"))
      (node (ref "RLA6") (pin "6") (pinfunction "6_6") (pintype "bidirectional"))
      (node (ref "RLA7") (pin "6") (pinfunction "6_6") (pintype "bidirectional"))
      (node (ref "RLA8") (pin "6") (pinfunction "6_6") (pintype "bidirectional"))
      (node (ref "RLA9") (pin "6") (pinfunction "6_6") (pintype "bidirectional"))
      (node (ref "SW1") (pin "3") (pinfunction "3_3") (pintype "passive"))
      (node (ref "SW1") (pin "4") (pinfunction "4_4") (pintype "passive"))
      (node (ref "TP1") (pin "TP") (pinfunction "TP_TP") (pintype "input"))
      (node (ref "VREG3.3") (pin "2") (pinfunction "GND_2") (pintype "passive"))
      (node (ref "VREG5.0") (pin "2") (pinfunction "GND_2") (pintype "passive"))
      (node (ref "ZD1") (pin "A") (pinfunction "A_A") (pintype "passive"))
      (node (ref "ZD10") (pin "A") (pinfunction "A_A") (pintype "passive"))
      (node (ref "ZD11") (pin "A") (pinfunction "A_A") (pintype "passive"))
      (node (ref "ZD2") (pin "A") (pinfunction "A_A") (pintype "passive"))
      (node (ref "ZD3") (pin "A") (pinfunction "A_A") (pintype "passive"))
      (node (ref "ZD4") (pin "A") (pinfunction "A_A") (pintype "passive"))
      (node (ref "ZD5") (pin "A") (pinfunction "A_A") (pintype "passive"))
      (node (ref "ZD6") (pin "A") (pinfunction "A_A") (pintype "passive"))
      (node (ref "ZD7") (pin "A") (pinfunction "A_A") (pintype "passive"))
      (node (ref "ZD8") (pin "A") (pinfunction "A_A") (pintype "passive"))
      (node (ref "ZD9") (pin "A") (pinfunction "A_A") (pintype "passive"))
    )
    (net (code "60") (name "Net-(D1-PadA)") (class "Default")
      (node (ref "D1") (pin "A") (pinfunction "A_A") (pintype "passive"))
      (node (ref "MOSFET") (pin "D") (pinfunction "D_D") (pintype "passive"))
    )
    (net (code "61") (name "Net-(D2-PadC)") (class "Default")
      (node (ref "D2") (pin "C") (pinfunction "C_C") (pintype "passive"))
      (node (ref "PTC1") (pin "1") (pinfunction "1_1") (pintype "bidirectional"))
    )
    (net (code "62") (name "Net-(IC1-XCK1{slash}OC1B{slash}PCINT28)") (class "Default")
      (node (ref "IC1") (pin "18") (pinfunction "XCK1/OC1B/PCINT28_18") (pintype "bidirectional"))
      (node (ref "R16") (pin "1") (pinfunction "1_1") (pintype "bidirectional"))
    )
    (net (code "63") (name "Net-(IC1-XTAL1)") (class "Default")
      (node (ref "C10") (pin "2") (pinfunction "2_2") (pintype "passive"))
      (node (ref "IC1") (pin "13") (pinfunction "XTAL1_13") (pintype "bidirectional"))
      (node (ref "XTAL") (pin "2") (pinfunction "2_2") (pintype "passive"))
    )
    (net (code "64") (name "Net-(IC1-XTAL2)") (class "Default")
      (node (ref "C7") (pin "1") (pinfunction "1_1") (pintype "passive"))
      (node (ref "IC1") (pin "12") (pinfunction "XTAL2_12") (pintype "bidirectional"))
      (node (ref "XTAL") (pin "1") (pinfunction "1_1") (pintype "passive"))
    )
    (net (code "65") (name "Net-(LED-PadA)") (class "Default")
      (node (ref "LED") (pin "A") (pinfunction "A_A") (pintype "passive"))
      (node (ref "R16") (pin "2") (pinfunction "2_2") (pintype "bidirectional"))
    )
    (net (code "66") (name "Net-(Q1-B)") (class "Default")
      (node (ref "Q1") (pin "2") (pinfunction "B_2") (pintype "passive"))
      (node (ref "R2") (pin "2") (pinfunction "2_2") (pintype "bidirectional"))
    )
    (net (code "67") (name "Net-(Q1-C)") (class "Default")
      (node (ref "MOSFET") (pin "G") (pinfunction "G_G") (pintype "passive"))
      (node (ref "Q1") (pin "1") (pinfunction "C_1") (pintype "passive"))
      (node (ref "R5") (pin "1") (pinfunction "1_1") (pintype "bidirectional"))
    )
    (net (code "68") (name "Net-(R6-Pad1)") (class "Default")
      (node (ref "R6") (pin "1") (pinfunction "1_1") (pintype "bidirectional"))
      (node (ref "R7") (pin "1") (pinfunction "1_1") (pintype "bidirectional"))
      (node (ref "SW1") (pin "1") (pinfunction "1_1") (pintype "passive"))
      (node (ref "SW1") (pin "2") (pinfunction "2_2") (pintype "passive"))
    )
    (net (code "69") (name "Net-(VREG5.0-VI)") (class "Default")
      (node (ref "C1") (pin "+") (pinfunction "+_+") (pintype "passive"))
      (node (ref "C4") (pin "+") (pinfunction "+_+") (pintype "passive"))
      (node (ref "PTC1") (pin "2") (pinfunction "2_2") (pintype "bidirectional"))
      (node (ref "VREG5.0") (pin "1") (pinfunction "VI_1") (pintype "input"))
    )
    (net (code "70") (name "unconnected-(ACCELEROM.-Pad0GD)") (class "Default")
      (node (ref "ACCELEROM.") (pin "0GD") (pinfunction "0GD_0GD") (pintype "bidirectional"))
    )
    (net (code "71") (name "unconnected-(ACCELEROM.-PadGSEL)") (class "Default")
      (node (ref "ACCELEROM.") (pin "GSEL") (pinfunction "GSEL_GSEL") (pintype "bidirectional"))
    )
    (net (code "72") (name "unconnected-(ACCELEROM.-PadST)") (class "Default")
      (node (ref "ACCELEROM.") (pin "ST") (pinfunction "ST_ST") (pintype "bidirectional"))
    )
    (net (code "73") (name "unconnected-(RLA1-Pad1)") (class "Default")
      (node (ref "RLA1") (pin "1") (pinfunction "1_1") (pintype "bidirectional"))
    )
    (net (code "74") (name "unconnected-(RLA1-Pad7)") (class "Default")
      (node (ref "RLA1") (pin "7") (pinfunction "7_7") (pintype "bidirectional"))
    )
    (net (code "75") (name "unconnected-(RLA1-Pad9)") (class "Default")
      (node (ref "RLA1") (pin "9") (pinfunction "9_9") (pintype "bidirectional"))
    )
    (net (code "76") (name "unconnected-(RLA1-Pad13)") (class "Default")
      (node (ref "RLA1") (pin "13") (pinfunction "13_13") (pintype "bidirectional"))
    )
    (net (code "77") (name "unconnected-(RLA2-Pad7)") (class "Default")
      (node (ref "RLA2") (pin "7") (pinfunction "7_7") (pintype "bidirectional"))
    )
    (net (code "78") (name "unconnected-(RLA2-Pad9)") (class "Default")
      (node (ref "RLA2") (pin "9") (pinfunction "9_9") (pintype "bidirectional"))
    )
    (net (code "79") (name "unconnected-(RLA2-Pad13)") (class "Default")
      (node (ref "RLA2") (pin "13") (pinfunction "13_13") (pintype "bidirectional"))
    )
    (net (code "80") (name "unconnected-(RLA3-Pad1)") (class "Default")
      (node (ref "RLA3") (pin "1") (pinfunction "1_1") (pintype "bidirectional"))
    )
    (net (code "81") (name "unconnected-(RLA3-Pad7)") (class "Default")
      (node (ref "RLA3") (pin "7") (pinfunction "7_7") (pintype "bidirectional"))
    )
    (net (code "82") (name "unconnected-(RLA3-Pad9)") (class "Default")
      (node (ref "RLA3") (pin "9") (pinfunction "9_9") (pintype "bidirectional"))
    )
    (net (code "83") (name "unconnected-(RLA3-Pad13)") (class "Default")
      (node (ref "RLA3") (pin "13") (pinfunction "13_13") (pintype "bidirectional"))
    )
    (net (code "84") (name "unconnected-(RLA4-Pad7)") (class "Default")
      (node (ref "RLA4") (pin "7") (pinfunction "7_7") (pintype "bidirectional"))
    )
    (net (code "85") (name "unconnected-(RLA4-Pad9)") (class "Default")
      (node (ref "RLA4") (pin "9") (pinfunction "9_9") (pintype "bidirectional"))
    )
    (net (code "86") (name "unconnected-(RLA4-Pad13)") (class "Default")
      (node (ref "RLA4") (pin "13") (pinfunction "13_13") (pintype "bidirectional"))
    )
    (net (code "87") (name "unconnected-(RLA5-Pad1)") (class "Default")
      (node (ref "RLA5") (pin "1") (pinfunction "1_1") (pintype "bidirectional"))
    )
    (net (code "88") (name "unconnected-(RLA5-Pad7)") (class "Default")
      (node (ref "RLA5") (pin "7") (pinfunction "7_7") (pintype "bidirectional"))
    )
    (net (code "89") (name "unconnected-(RLA5-Pad9)") (class "Default")
      (node (ref "RLA5") (pin "9") (pinfunction "9_9") (pintype "bidirectional"))
    )
    (net (code "90") (name "unconnected-(RLA5-Pad13)") (class "Default")
      (node (ref "RLA5") (pin "13") (pinfunction "13_13") (pintype "bidirectional"))
    )
    (net (code "91") (name "unconnected-(RLA6-Pad1)") (class "Default")
      (node (ref "RLA6") (pin "1") (pinfunction "1_1") (pintype "bidirectional"))
    )
    (net (code "92") (name "unconnected-(RLA6-Pad7)") (class "Default")
      (node (ref "RLA6") (pin "7") (pinfunction "7_7") (pintype "bidirectional"))
    )
    (net (code "93") (name "unconnected-(RLA6-Pad9)") (class "Default")
      (node (ref "RLA6") (pin "9") (pinfunction "9_9") (pintype "bidirectional"))
    )
    (net (code "94") (name "unconnected-(RLA6-Pad13)") (class "Default")
      (node (ref "RLA6") (pin "13") (pinfunction "13_13") (pintype "bidirectional"))
    )
    (net (code "95") (name "unconnected-(RLA7-Pad1)") (class "Default")
      (node (ref "RLA7") (pin "1") (pinfunction "1_1") (pintype "bidirectional"))
    )
    (net (code "96") (name "unconnected-(RLA7-Pad7)") (class "Default")
      (node (ref "RLA7") (pin "7") (pinfunction "7_7") (pintype "bidirectional"))
    )
    (net (code "97") (name "unconnected-(RLA7-Pad9)") (class "Default")
      (node (ref "RLA7") (pin "9") (pinfunction "9_9") (pintype "bidirectional"))
    )
    (net (code "98") (name "unconnected-(RLA7-Pad13)") (class "Default")
      (node (ref "RLA7") (pin "13") (pinfunction "13_13") (pintype "bidirectional"))
    )
    (net (code "99") (name "unconnected-(RLA8-Pad1)") (class "Default")
      (node (ref "RLA8") (pin "1") (pinfunction "1_1") (pintype "bidirectional"))
    )
    (net (code "100") (name "unconnected-(RLA8-Pad8)") (class "Default")
      (node (ref "RLA8") (pin "8") (pinfunction "8_8") (pintype "bidirectional"))
    )
    (net (code "101") (name "unconnected-(RLA8-Pad9)") (class "Default")
      (node (ref "RLA8") (pin "9") (pinfunction "9_9") (pintype "bidirectional"))
    )
    (net (code "102") (name "unconnected-(RLA8-Pad13)") (class "Default")
      (node (ref "RLA8") (pin "13") (pinfunction "13_13") (pintype "bidirectional"))
    )
    (net (code "103") (name "unconnected-(RLA9-Pad1)") (class "Default")
      (node (ref "RLA9") (pin "1") (pinfunction "1_1") (pintype "bidirectional"))
    )
    (net (code "104") (name "unconnected-(RLA9-Pad8)") (class "Default")
      (node (ref "RLA9") (pin "8") (pinfunction "8_8") (pintype "bidirectional"))
    )
    (net (code "105") (name "unconnected-(RLA9-Pad9)") (class "Default")
      (node (ref "RLA9") (pin "9") (pinfunction "9_9") (pintype "bidirectional"))
    )
    (net (code "106") (name "unconnected-(RLA9-Pad13)") (class "Default")
      (node (ref "RLA9") (pin "13") (pinfunction "13_13") (pintype "bidirectional"))
    )
  )
)
